# vram_board.net
KiCad netlist of a schematic drawn in EAGLE
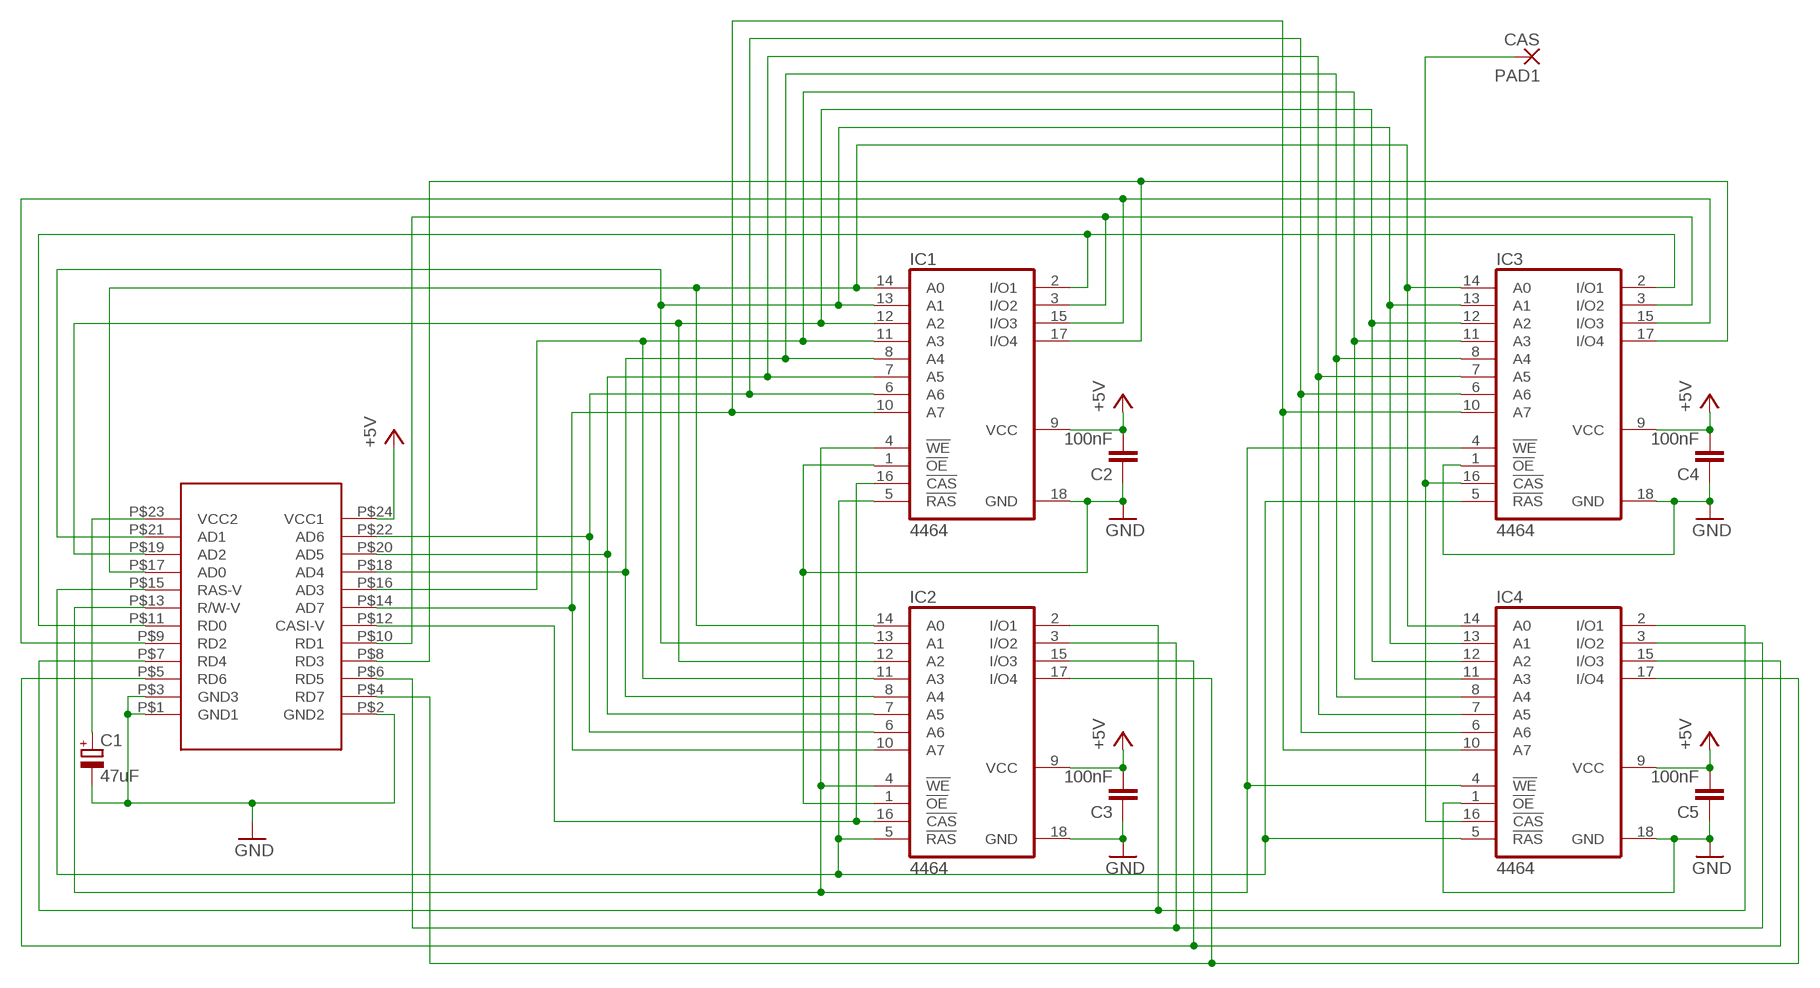
[diagram p0: schematic, sheet 1]

(export (version "E")
  (design (tool "Eeschema 10.0.6"))
  (components
    (comp (ref "C1")
      (value "47uF")
      (footprint "eagle-import:E2-5")
      (libsource (lib "eagle-import") (part "CPOL-EUE2-5"))
    )
    (comp (ref "C2")
      (value "100nF")
      (footprint "eagle-import:C050-025X075")
      (libsource (lib "eagle-import") (part "C-EU050-025X075"))
    )
    (comp (ref "C3")
      (value "100nF")
      (footprint "eagle-import:C050-025X075")
      (libsource (lib "eagle-import") (part "C-EU050-025X075"))
    )
    (comp (ref "C4")
      (value "100nF")
      (footprint "eagle-import:C050-025X075")
      (libsource (lib "eagle-import") (part "C-EU050-025X075"))
    )
    (comp (ref "C5")
      (value "100nF")
      (footprint "eagle-import:C050-025X075")
      (libsource (lib "eagle-import") (part "C-EU050-025X075"))
    )
    (comp (ref "IC1")
      (value "4464")
      (footprint "eagle-import:DIL18")
      (libsource (lib "eagle-import") (part "41464C"))
    )
    (comp (ref "IC2")
      (value "4464")
      (footprint "eagle-import:DIL18")
      (libsource (lib "eagle-import") (part "41464C"))
    )
    (comp (ref "IC3")
      (value "4464")
      (footprint "eagle-import:DIL18")
      (libsource (lib "eagle-import") (part "41464C"))
    )
    (comp (ref "IC4")
      (value "4464")
      (footprint "eagle-import:DIL18")
      (libsource (lib "eagle-import") (part "41464C"))
    )
    (comp (ref "PAD1")
      (value "CAS")
      (footprint "eagle-import:1,6_0,9")
      (libsource (lib "eagle-import") (part "1,6/0,9"))
    )
    (comp (ref "U$1")
      (value "CN24DR")
      (footprint "eagle-import:VRAM_CONN")
      (libsource (lib "eagle-import") (part "CN24DR"))
    )
  )
  (nets
    (net (code "1") (name "+5V") (class "Default")
      (node (ref "C2") (pin "2") (pinfunction "2_2") (pintype "passive"))
      (node (ref "C3") (pin "2") (pinfunction "2_2") (pintype "passive"))
      (node (ref "C4") (pin "2") (pinfunction "2_2") (pintype "passive"))
      (node (ref "C5") (pin "2") (pinfunction "2_2") (pintype "passive"))
      (node (ref "IC1") (pin "9") (pinfunction "VCC_9") (pintype "power_in"))
      (node (ref "IC2") (pin "9") (pinfunction "VCC_9") (pintype "power_in"))
      (node (ref "IC3") (pin "9") (pinfunction "VCC_9") (pintype "power_in"))
      (node (ref "IC4") (pin "9") (pinfunction "VCC_9") (pintype "power_in"))
      (node (ref "U$1") (pin "P$24") (pinfunction "VCC1_P$24") (pintype "bidirectional"))
    )
    (net (code "2") (name "GND") (class "Default")
      (node (ref "C1") (pin "-") (pinfunction "-_-") (pintype "passive"))
      (node (ref "C2") (pin "1") (pinfunction "1_1") (pintype "passive"))
      (node (ref "C3") (pin "1") (pinfunction "1_1") (pintype "passive"))
      (node (ref "C4") (pin "1") (pinfunction "1_1") (pintype "passive"))
      (node (ref "C5") (pin "1") (pinfunction "1_1") (pintype "passive"))
      (node (ref "IC1") (pin "1") (pinfunction "~{OE}_1") (pintype "input"))
      (node (ref "IC1") (pin "18") (pinfunction "GND_18") (pintype "power_in"))
      (node (ref "IC2") (pin "1") (pinfunction "~{OE}_1") (pintype "input"))
      (node (ref "IC2") (pin "18") (pinfunction "GND_18") (pintype "power_in"))
      (node (ref "IC3") (pin "1") (pinfunction "~{OE}_1") (pintype "input"))
      (node (ref "IC3") (pin "18") (pinfunction "GND_18") (pintype "power_in"))
      (node (ref "IC4") (pin "1") (pinfunction "~{OE}_1") (pintype "input"))
      (node (ref "IC4") (pin "18") (pinfunction "GND_18") (pintype "power_in"))
      (node (ref "U$1") (pin "P$1") (pinfunction "GND1_P$1") (pintype "bidirectional"))
      (node (ref "U$1") (pin "P$2") (pinfunction "GND2_P$2") (pintype "bidirectional"))
      (node (ref "U$1") (pin "P$3") (pinfunction "GND3_P$3") (pintype "bidirectional"))
    )
    (net (code "3") (name "Net-(IC1-A0)") (class "Default")
      (node (ref "IC1") (pin "14") (pinfunction "A0_14") (pintype "input"))
      (node (ref "IC2") (pin "14") (pinfunction "A0_14") (pintype "input"))
      (node (ref "IC3") (pin "14") (pinfunction "A0_14") (pintype "input"))
      (node (ref "IC4") (pin "14") (pinfunction "A0_14") (pintype "input"))
      (node (ref "U$1") (pin "P$17") (pinfunction "AD0_P$17") (pintype "bidirectional"))
    )
    (net (code "4") (name "Net-(IC1-A1)") (class "Default")
      (node (ref "IC1") (pin "13") (pinfunction "A1_13") (pintype "input"))
      (node (ref "IC2") (pin "13") (pinfunction "A1_13") (pintype "input"))
      (node (ref "IC3") (pin "13") (pinfunction "A1_13") (pintype "input"))
      (node (ref "IC4") (pin "13") (pinfunction "A1_13") (pintype "input"))
      (node (ref "U$1") (pin "P$21") (pinfunction "AD1_P$21") (pintype "bidirectional"))
    )
    (net (code "5") (name "Net-(IC1-A2)") (class "Default")
      (node (ref "IC1") (pin "12") (pinfunction "A2_12") (pintype "input"))
      (node (ref "IC2") (pin "12") (pinfunction "A2_12") (pintype "input"))
      (node (ref "IC3") (pin "12") (pinfunction "A2_12") (pintype "input"))
      (node (ref "IC4") (pin "12") (pinfunction "A2_12") (pintype "input"))
      (node (ref "U$1") (pin "P$19") (pinfunction "AD2_P$19") (pintype "bidirectional"))
    )
    (net (code "6") (name "Net-(IC1-A3)") (class "Default")
      (node (ref "IC1") (pin "11") (pinfunction "A3_11") (pintype "input"))
      (node (ref "IC2") (pin "11") (pinfunction "A3_11") (pintype "input"))
      (node (ref "IC3") (pin "11") (pinfunction "A3_11") (pintype "input"))
      (node (ref "IC4") (pin "11") (pinfunction "A3_11") (pintype "input"))
      (node (ref "U$1") (pin "P$16") (pinfunction "AD3_P$16") (pintype "bidirectional"))
    )
    (net (code "7") (name "Net-(IC1-A4)") (class "Default")
      (node (ref "IC1") (pin "8") (pinfunction "A4_8") (pintype "input"))
      (node (ref "IC2") (pin "8") (pinfunction "A4_8") (pintype "input"))
      (node (ref "IC3") (pin "8") (pinfunction "A4_8") (pintype "input"))
      (node (ref "IC4") (pin "8") (pinfunction "A4_8") (pintype "input"))
      (node (ref "U$1") (pin "P$18") (pinfunction "AD4_P$18") (pintype "bidirectional"))
    )
    (net (code "8") (name "Net-(IC1-A5)") (class "Default")
      (node (ref "IC1") (pin "7") (pinfunction "A5_7") (pintype "input"))
      (node (ref "IC2") (pin "7") (pinfunction "A5_7") (pintype "input"))
      (node (ref "IC3") (pin "7") (pinfunction "A5_7") (pintype "input"))
      (node (ref "IC4") (pin "7") (pinfunction "A5_7") (pintype "input"))
      (node (ref "U$1") (pin "P$20") (pinfunction "AD5_P$20") (pintype "bidirectional"))
    )
    (net (code "9") (name "Net-(IC1-A6)") (class "Default")
      (node (ref "IC1") (pin "6") (pinfunction "A6_6") (pintype "input"))
      (node (ref "IC2") (pin "6") (pinfunction "A6_6") (pintype "input"))
      (node (ref "IC3") (pin "6") (pinfunction "A6_6") (pintype "input"))
      (node (ref "IC4") (pin "6") (pinfunction "A6_6") (pintype "input"))
      (node (ref "U$1") (pin "P$22") (pinfunction "AD6_P$22") (pintype "bidirectional"))
    )
    (net (code "10") (name "Net-(IC1-A7)") (class "Default")
      (node (ref "IC1") (pin "10") (pinfunction "A7_10") (pintype "input"))
      (node (ref "IC2") (pin "10") (pinfunction "A7_10") (pintype "input"))
      (node (ref "IC3") (pin "10") (pinfunction "A7_10") (pintype "input"))
      (node (ref "IC4") (pin "10") (pinfunction "A7_10") (pintype "input"))
      (node (ref "U$1") (pin "P$14") (pinfunction "AD7_P$14") (pintype "bidirectional"))
    )
    (net (code "11") (name "Net-(IC1-I{slash}O1)") (class "Default")
      (node (ref "IC1") (pin "2") (pinfunction "I/O1_2") (pintype "bidirectional"))
      (node (ref "IC3") (pin "2") (pinfunction "I/O1_2") (pintype "bidirectional"))
      (node (ref "U$1") (pin "P$11") (pinfunction "RD0_P$11") (pintype "bidirectional"))
    )
    (net (code "12") (name "Net-(IC1-I{slash}O2)") (class "Default")
      (node (ref "IC1") (pin "3") (pinfunction "I/O2_3") (pintype "bidirectional"))
      (node (ref "IC3") (pin "3") (pinfunction "I/O2_3") (pintype "bidirectional"))
      (node (ref "U$1") (pin "P$10") (pinfunction "RD1_P$10") (pintype "bidirectional"))
    )
    (net (code "13") (name "Net-(IC1-I{slash}O3)") (class "Default")
      (node (ref "IC1") (pin "15") (pinfunction "I/O3_15") (pintype "bidirectional"))
      (node (ref "IC3") (pin "15") (pinfunction "I/O3_15") (pintype "bidirectional"))
      (node (ref "U$1") (pin "P$9") (pinfunction "RD2_P$9") (pintype "bidirectional"))
    )
    (net (code "14") (name "Net-(IC1-I{slash}O4)") (class "Default")
      (node (ref "IC1") (pin "17") (pinfunction "I/O4_17") (pintype "bidirectional"))
      (node (ref "IC3") (pin "17") (pinfunction "I/O4_17") (pintype "bidirectional"))
      (node (ref "U$1") (pin "P$8") (pinfunction "RD3_P$8") (pintype "bidirectional"))
    )
    (net (code "15") (name "Net-(IC1-~{CAS})") (class "Default")
      (node (ref "IC1") (pin "16") (pinfunction "~{CAS}_16") (pintype "input"))
      (node (ref "IC2") (pin "16") (pinfunction "~{CAS}_16") (pintype "input"))
      (node (ref "U$1") (pin "P$12") (pinfunction "CASI-V_P$12") (pintype "bidirectional"))
    )
    (net (code "16") (name "Net-(IC1-~{RAS})") (class "Default")
      (node (ref "IC1") (pin "5") (pinfunction "~{RAS}_5") (pintype "input"))
      (node (ref "IC2") (pin "5") (pinfunction "~{RAS}_5") (pintype "input"))
      (node (ref "IC3") (pin "5") (pinfunction "~{RAS}_5") (pintype "input"))
      (node (ref "IC4") (pin "5") (pinfunction "~{RAS}_5") (pintype "input"))
      (node (ref "U$1") (pin "P$15") (pinfunction "RAS-V_P$15") (pintype "bidirectional"))
    )
    (net (code "17") (name "Net-(IC1-~{WE})") (class "Default")
      (node (ref "IC1") (pin "4") (pinfunction "~{WE}_4") (pintype "input"))
      (node (ref "IC2") (pin "4") (pinfunction "~{WE}_4") (pintype "input"))
      (node (ref "IC3") (pin "4") (pinfunction "~{WE}_4") (pintype "input"))
      (node (ref "IC4") (pin "4") (pinfunction "~{WE}_4") (pintype "input"))
      (node (ref "U$1") (pin "P$13") (pinfunction "R/W-V_P$13") (pintype "bidirectional"))
    )
    (net (code "18") (name "Net-(IC2-I{slash}O1)") (class "Default")
      (node (ref "IC2") (pin "2") (pinfunction "I/O1_2") (pintype "bidirectional"))
      (node (ref "IC4") (pin "2") (pinfunction "I/O1_2") (pintype "bidirectional"))
      (node (ref "U$1") (pin "P$7") (pinfunction "RD4_P$7") (pintype "bidirectional"))
    )
    (net (code "19") (name "Net-(IC2-I{slash}O2)") (class "Default")
      (node (ref "IC2") (pin "3") (pinfunction "I/O2_3") (pintype "bidirectional"))
      (node (ref "IC4") (pin "3") (pinfunction "I/O2_3") (pintype "bidirectional"))
      (node (ref "U$1") (pin "P$6") (pinfunction "RD5_P$6") (pintype "bidirectional"))
    )
    (net (code "20") (name "Net-(IC2-I{slash}O3)") (class "Default")
      (node (ref "IC2") (pin "15") (pinfunction "I/O3_15") (pintype "bidirectional"))
      (node (ref "IC4") (pin "15") (pinfunction "I/O3_15") (pintype "bidirectional"))
      (node (ref "U$1") (pin "P$5") (pinfunction "RD6_P$5") (pintype "bidirectional"))
    )
    (net (code "21") (name "Net-(IC2-I{slash}O4)") (class "Default")
      (node (ref "IC2") (pin "17") (pinfunction "I/O4_17") (pintype "bidirectional"))
      (node (ref "IC4") (pin "17") (pinfunction "I/O4_17") (pintype "bidirectional"))
      (node (ref "U$1") (pin "P$4") (pinfunction "RD7_P$4") (pintype "bidirectional"))
    )
    (net (code "22") (name "Net-(IC3-~{CAS})") (class "Default")
      (node (ref "IC3") (pin "16") (pinfunction "~{CAS}_16") (pintype "input"))
      (node (ref "IC4") (pin "16") (pinfunction "~{CAS}_16") (pintype "input"))
      (node (ref "PAD1") (pin "1") (pinfunction "P_1") (pintype "passive"))
    )
    (net (code "23") (name "Net-(U$1-VCC2)") (class "Default")
      (node (ref "C1") (pin "+") (pinfunction "+_+") (pintype "passive"))
      (node (ref "U$1") (pin "P$23") (pinfunction "VCC2_P$23") (pintype "bidirectional"))
    )
  )
)
